# Protect.net
KiCad netlist of a schematic drawn in Altium Designer
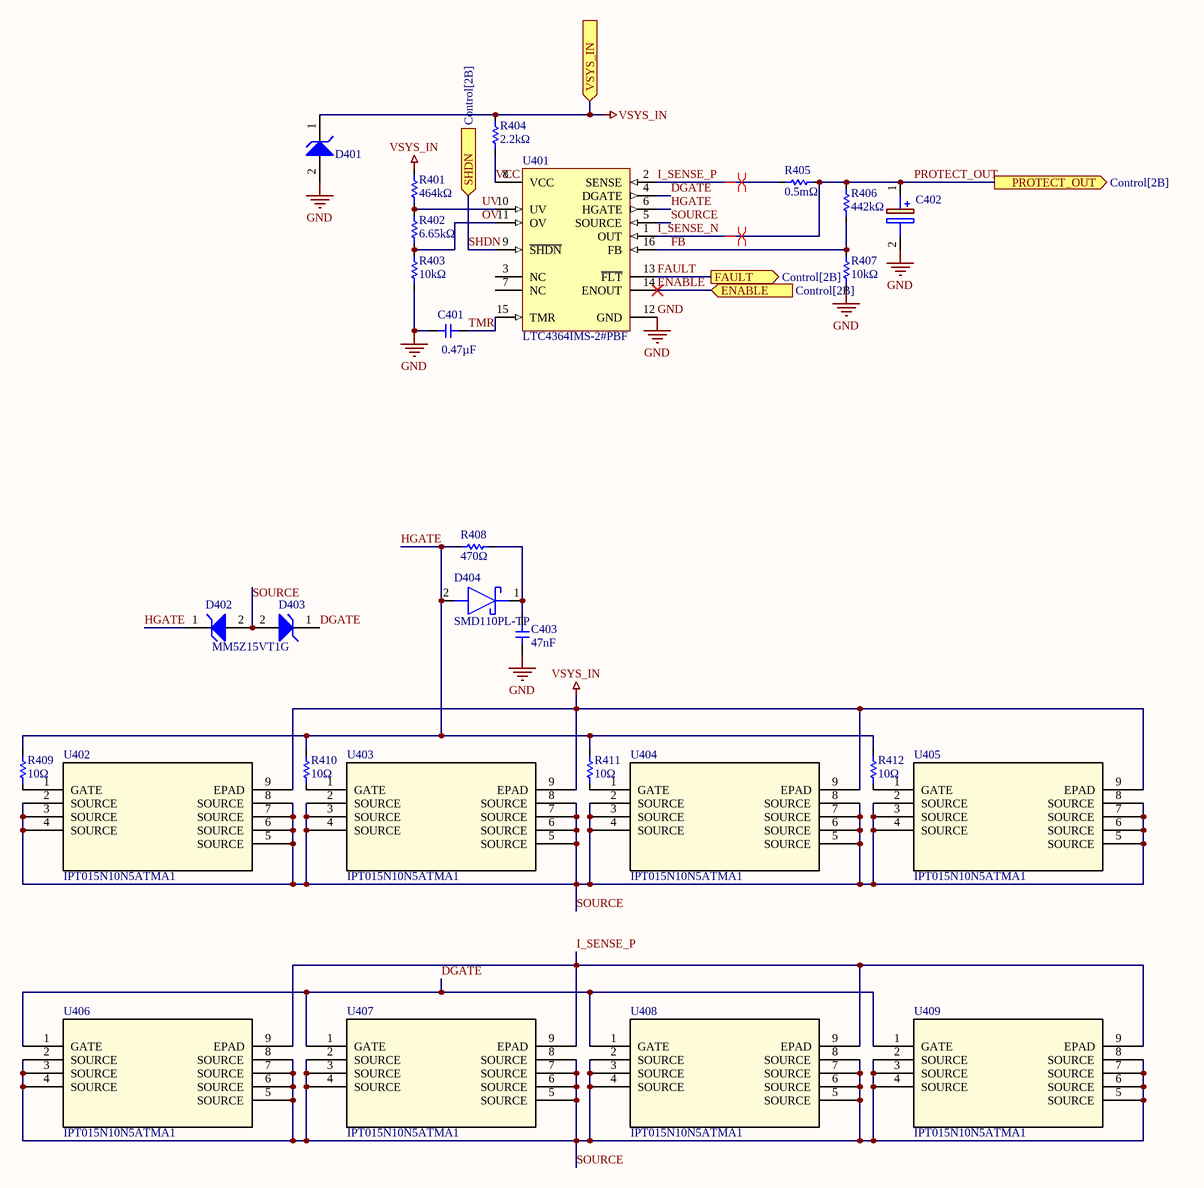
[diagram p0: Protect.SchDoc]

(export (version "E")
  (design (tool "Eeschema 10.0.6"))
  (components
    (comp (ref "C401")
      (value "non-polar_Capacitor")
      (footprint "1210")
      (description "SMD type ceramic capacitor")
      (fields
        (field (name "VOLTAGE") "50V")
        (field (name "CAPACITANCE") "0.47µF")
        (field (name "SOURCE") "robit_passive.SchLib")
      )
      (libsource (lib "robit circuit") (part "Capacitor"))
    )
    (comp (ref "C402")
      (value "B41858C9477M000")
      (footprint "SamacSys:CAPPRD750W90D1800H3700")
      (description "Capacitor Polarised")
      (fields (field (name "MOUSER PART NUMBER") "871-B41858C9477M"))
      (libsource (lib "*") (part "B41858C9477M000"))
    )
    (comp (ref "C403")
      (value "non-polar_Capacitor")
      (footprint "1210")
      (description "SMD type ceramic capacitor")
      (fields
        (field (name "VOLTAGE") "50V")
        (field (name "CAPACITANCE") "47nF")
        (field (name "SOURCE") "robit_passive.SchLib")
      )
      (libsource (lib "robit circuit") (part "Capacitor"))
    )
    (comp (ref "D401")
      (value "1SMB5945BT3G")
      (footprint "ONSC-SMB-2-403A-03_H_V")
      (description "3 W Zener Voltage Regulator, 2-Pin SMB, Pb-Free, Tape and Reel")
      (fields (field (name "MANUFACTURER") "On Semiconductor"))
      (libsource (lib "Altium Content Vault") (part "ONSC-K1A2-2"))
    )
    (comp (ref "D402")
      (value "MM5Z15VT1G")
      (footprint "ONSC-SOD-523-2-502-01_V")
      (description "Zener Voltage Regulator, 500 mW, 2-Pin SOD-523, Pb-Free, Tape and Reel")
      (fields (field (name "MANUFACTURER") "On Semiconductor"))
      (libsource (lib "Altium Content Vault") (part "ONSC-K1A2-2"))
    )
    (comp (ref "D403")
      (value "MM5Z15VT1G")
      (footprint "ONSC-SOD-523-2-502-01_V")
      (description "Zener Voltage Regulator, 500 mW, 2-Pin SOD-523, Pb-Free, Tape and Reel")
      (fields (field (name "MANUFACTURER") "On Semiconductor"))
      (libsource (lib "Altium Content Vault") (part "ONSC-K1A2-2"))
    )
    (comp (ref "D404")
      (value "SMD110PL-TP")
      (footprint "SamacSys:SODFL3616X135N")
      (description "Schottky Diode")
      (fields (field (name "MOUSER PART NUMBER") "833-SMD110PL-TP"))
      (libsource (lib "*") (part "SMD110PL-TP"))
    )
    (comp (ref "R401") (value "464kΩ") (footprint "SMD_0603") (libsource (lib "Resistor") (part "Resistor")))
    (comp (ref "R402") (value "6.65kΩ") (footprint "SMD_0603") (libsource (lib "Resistor") (part "Resistor")))
    (comp (ref "R403") (value "10kΩ") (footprint "SMD_0603") (libsource (lib "Resistor") (part "Resistor")))
    (comp (ref "R404") (value "2.2kΩ") (footprint "SMD_2512") (libsource (lib "Resistor") (part "Resistor")))
    (comp (ref "R405") (value "0.5mΩ") (footprint "SMD_2512") (libsource (lib "Resistor") (part "Resistor")))
    (comp (ref "R406") (value "442kΩ") (footprint "SMD_0603") (libsource (lib "Resistor") (part "Resistor")))
    (comp (ref "R407") (value "10kΩ") (footprint "SMD_0603") (libsource (lib "Resistor") (part "Resistor")))
    (comp (ref "R408")
      (value "470Ω")
      (footprint "SMD_0603")
      (description "0.1W, 0603")
      (libsource (lib "Resistor") (part "Resistor"))
    )
    (comp (ref "R409") (value "10Ω") (footprint "SMD_0603") (libsource (lib "Resistor") (part "Resistor")))
    (comp (ref "R410") (value "10Ω") (footprint "SMD_0603") (libsource (lib "Resistor") (part "Resistor")))
    (comp (ref "R411") (value "10Ω") (footprint "SMD_0603") (libsource (lib "Resistor") (part "Resistor")))
    (comp (ref "R412") (value "10Ω") (footprint "SMD_0603") (libsource (lib "Resistor") (part "Resistor")))
    (comp (ref "U401")
      (value "LTC4364IMS-2#PBF")
      (footprint "LT-MS-16_M")
      (description "Surge Stopper with Ideal Diode, 4 to 80 V Vin, 16-pin SOP (MS-16), -40 to 85 degC, Pb-Free")
      (fields (field (name "MANUFACTURER") "Linear Technology"))
      (libsource (lib "Altium Content Vault") (part "LT-LTC4364-S-16"))
    )
    (comp (ref "U402")
      (value "IPT015N10N5ATMA1")
      (footprint "PG-HSOF-8-1_INF")
      (fields (field (name "COPYRIGHT") "Copyright (C) 2025 Ultra Librarian. All rights reserved."))
      (libsource (lib "IPT015N10N5ATMA1") (part "IPT015N10N5ATMA1"))
    )
    (comp (ref "U403")
      (value "IPT015N10N5ATMA1")
      (footprint "PG-HSOF-8-1_INF")
      (fields (field (name "COPYRIGHT") "Copyright (C) 2025 Ultra Librarian. All rights reserved."))
      (libsource (lib "IPT015N10N5ATMA1") (part "IPT015N10N5ATMA1"))
    )
    (comp (ref "U404")
      (value "IPT015N10N5ATMA1")
      (footprint "PG-HSOF-8-1_INF")
      (fields (field (name "COPYRIGHT") "Copyright (C) 2025 Ultra Librarian. All rights reserved."))
      (libsource (lib "IPT015N10N5ATMA1") (part "IPT015N10N5ATMA1"))
    )
    (comp (ref "U405")
      (value "IPT015N10N5ATMA1")
      (footprint "PG-HSOF-8-1_INF")
      (fields (field (name "COPYRIGHT") "Copyright (C) 2025 Ultra Librarian. All rights reserved."))
      (libsource (lib "IPT015N10N5ATMA1") (part "IPT015N10N5ATMA1"))
    )
    (comp (ref "U406")
      (value "IPT015N10N5ATMA1")
      (footprint "PG-HSOF-8-1_INF")
      (fields (field (name "COPYRIGHT") "Copyright (C) 2025 Ultra Librarian. All rights reserved."))
      (libsource (lib "IPT015N10N5ATMA1") (part "IPT015N10N5ATMA1"))
    )
    (comp (ref "U407")
      (value "IPT015N10N5ATMA1")
      (footprint "PG-HSOF-8-1_INF")
      (fields (field (name "COPYRIGHT") "Copyright (C) 2025 Ultra Librarian. All rights reserved."))
      (libsource (lib "IPT015N10N5ATMA1") (part "IPT015N10N5ATMA1"))
    )
    (comp (ref "U408")
      (value "IPT015N10N5ATMA1")
      (footprint "PG-HSOF-8-1_INF")
      (fields (field (name "COPYRIGHT") "Copyright (C) 2025 Ultra Librarian. All rights reserved."))
      (libsource (lib "IPT015N10N5ATMA1") (part "IPT015N10N5ATMA1"))
    )
    (comp (ref "U409")
      (value "IPT015N10N5ATMA1")
      (footprint "PG-HSOF-8-1_INF")
      (fields (field (name "COPYRIGHT") "Copyright (C) 2025 Ultra Librarian. All rights reserved."))
      (libsource (lib "IPT015N10N5ATMA1") (part "IPT015N10N5ATMA1"))
    )
  )
  (nets
    (net (code "1") (name "/DGATE") (class "Default")
      (node (ref "D403") (pin "1") (pinfunction "K_1") (pintype "passive"))
      (node (ref "U401") (pin "4") (pinfunction "DGATE_4") (pintype "output"))
      (node (ref "U406") (pin "1") (pinfunction "GATE_1") (pintype "passive"))
      (node (ref "U407") (pin "1") (pinfunction "GATE_1") (pintype "passive"))
      (node (ref "U408") (pin "1") (pinfunction "GATE_1") (pintype "passive"))
      (node (ref "U409") (pin "1") (pinfunction "GATE_1") (pintype "passive"))
    )
    (net (code "2") (name "/ENABLE") (class "Default")
      (node (ref "U401") (pin "14") (pinfunction "ENOUT_14") (pintype "tri_state+no_connect"))
    )
    (net (code "3") (name "/FAULT") (class "Default")
      (node (ref "U401") (pin "13") (pinfunction "~{FLT}_13") (pintype "tri_state"))
    )
    (net (code "4") (name "/FB") (class "Default")
      (node (ref "R406") (pin "2") (pinfunction "2_2") (pintype "passive"))
      (node (ref "R407") (pin "1") (pinfunction "1_1") (pintype "passive"))
      (node (ref "U401") (pin "16") (pinfunction "FB_16") (pintype "input"))
    )
    (net (code "5") (name "/HGATE") (class "Default")
      (node (ref "D402") (pin "1") (pinfunction "K_1") (pintype "passive"))
      (node (ref "D404") (pin "2") (pinfunction "A_2") (pintype "passive"))
      (node (ref "R408") (pin "1") (pinfunction "1_1") (pintype "passive"))
      (node (ref "R409") (pin "1") (pinfunction "1_1") (pintype "passive"))
      (node (ref "R410") (pin "1") (pinfunction "1_1") (pintype "passive"))
      (node (ref "R411") (pin "1") (pinfunction "1_1") (pintype "passive"))
      (node (ref "R412") (pin "1") (pinfunction "1_1") (pintype "passive"))
      (node (ref "U401") (pin "6") (pinfunction "HGATE_6") (pintype "output"))
    )
    (net (code "6") (name "/I_SENSE_N") (class "Default")
      (node (ref "C402") (pin "1") (pinfunction "+_1") (pintype "passive"))
      (node (ref "R405") (pin "2") (pinfunction "2_2") (pintype "passive"))
      (node (ref "R406") (pin "1") (pinfunction "1_1") (pintype "passive"))
      (node (ref "U401") (pin "1") (pinfunction "OUT_1") (pintype "input"))
    )
    (net (code "7") (name "/I_SENSE_P") (class "Default")
      (node (ref "R405") (pin "1") (pinfunction "1_1") (pintype "passive"))
      (node (ref "U401") (pin "2") (pinfunction "SENSE_2") (pintype "input"))
      (node (ref "U406") (pin "9") (pinfunction "EPAD_9") (pintype "passive"))
      (node (ref "U407") (pin "9") (pinfunction "EPAD_9") (pintype "passive"))
      (node (ref "U408") (pin "9") (pinfunction "EPAD_9") (pintype "passive"))
      (node (ref "U409") (pin "9") (pinfunction "EPAD_9") (pintype "passive"))
    )
    (net (code "8") (name "/OV") (class "Default")
      (node (ref "R402") (pin "2") (pinfunction "2_2") (pintype "passive"))
      (node (ref "R403") (pin "1") (pinfunction "1_1") (pintype "passive"))
      (node (ref "U401") (pin "11") (pinfunction "OV_11") (pintype "input"))
    )
    (net (code "9") (name "/SHDN") (class "Default")
      (node (ref "U401") (pin "9") (pinfunction "~{SHDN}_9") (pintype "input"))
    )
    (net (code "10") (name "/SOURCE") (class "Default")
      (node (ref "D402") (pin "2") (pinfunction "A_2") (pintype "passive"))
      (node (ref "D403") (pin "2") (pinfunction "A_2") (pintype "passive"))
      (node (ref "U401") (pin "5") (pinfunction "SOURCE_5") (pintype "input"))
      (node (ref "U402") (pin "2") (pinfunction "SOURCE_2") (pintype "passive"))
      (node (ref "U402") (pin "3") (pinfunction "SOURCE_3") (pintype "passive"))
      (node (ref "U402") (pin "4") (pinfunction "SOURCE_4") (pintype "passive"))
      (node (ref "U402") (pin "5") (pinfunction "SOURCE_5") (pintype "passive"))
      (node (ref "U402") (pin "6") (pinfunction "SOURCE_6") (pintype "passive"))
      (node (ref "U402") (pin "7") (pinfunction "SOURCE_7") (pintype "passive"))
      (node (ref "U402") (pin "8") (pinfunction "SOURCE_8") (pintype "passive"))
      (node (ref "U403") (pin "2") (pinfunction "SOURCE_2") (pintype "passive"))
      (node (ref "U403") (pin "3") (pinfunction "SOURCE_3") (pintype "passive"))
      (node (ref "U403") (pin "4") (pinfunction "SOURCE_4") (pintype "passive"))
      (node (ref "U403") (pin "5") (pinfunction "SOURCE_5") (pintype "passive"))
      (node (ref "U403") (pin "6") (pinfunction "SOURCE_6") (pintype "passive"))
      (node (ref "U403") (pin "7") (pinfunction "SOURCE_7") (pintype "passive"))
      (node (ref "U403") (pin "8") (pinfunction "SOURCE_8") (pintype "passive"))
      (node (ref "U404") (pin "2") (pinfunction "SOURCE_2") (pintype "passive"))
      (node (ref "U404") (pin "3") (pinfunction "SOURCE_3") (pintype "passive"))
      (node (ref "U404") (pin "4") (pinfunction "SOURCE_4") (pintype "passive"))
      (node (ref "U404") (pin "5") (pinfunction "SOURCE_5") (pintype "passive"))
      (node (ref "U404") (pin "6") (pinfunction "SOURCE_6") (pintype "passive"))
      (node (ref "U404") (pin "7") (pinfunction "SOURCE_7") (pintype "passive"))
      (node (ref "U404") (pin "8") (pinfunction "SOURCE_8") (pintype "passive"))
      (node (ref "U405") (pin "2") (pinfunction "SOURCE_2") (pintype "passive"))
      (node (ref "U405") (pin "3") (pinfunction "SOURCE_3") (pintype "passive"))
      (node (ref "U405") (pin "4") (pinfunction "SOURCE_4") (pintype "passive"))
      (node (ref "U405") (pin "5") (pinfunction "SOURCE_5") (pintype "passive"))
      (node (ref "U405") (pin "6") (pinfunction "SOURCE_6") (pintype "passive"))
      (node (ref "U405") (pin "7") (pinfunction "SOURCE_7") (pintype "passive"))
      (node (ref "U405") (pin "8") (pinfunction "SOURCE_8") (pintype "passive"))
      (node (ref "U406") (pin "2") (pinfunction "SOURCE_2") (pintype "passive"))
      (node (ref "U406") (pin "3") (pinfunction "SOURCE_3") (pintype "passive"))
      (node (ref "U406") (pin "4") (pinfunction "SOURCE_4") (pintype "passive"))
      (node (ref "U406") (pin "5") (pinfunction "SOURCE_5") (pintype "passive"))
      (node (ref "U406") (pin "6") (pinfunction "SOURCE_6") (pintype "passive"))
      (node (ref "U406") (pin "7") (pinfunction "SOURCE_7") (pintype "passive"))
      (node (ref "U406") (pin "8") (pinfunction "SOURCE_8") (pintype "passive"))
      (node (ref "U407") (pin "2") (pinfunction "SOURCE_2") (pintype "passive"))
      (node (ref "U407") (pin "3") (pinfunction "SOURCE_3") (pintype "passive"))
      (node (ref "U407") (pin "4") (pinfunction "SOURCE_4") (pintype "passive"))
      (node (ref "U407") (pin "5") (pinfunction "SOURCE_5") (pintype "passive"))
      (node (ref "U407") (pin "6") (pinfunction "SOURCE_6") (pintype "passive"))
      (node (ref "U407") (pin "7") (pinfunction "SOURCE_7") (pintype "passive"))
      (node (ref "U407") (pin "8") (pinfunction "SOURCE_8") (pintype "passive"))
      (node (ref "U408") (pin "2") (pinfunction "SOURCE_2") (pintype "passive"))
      (node (ref "U408") (pin "3") (pinfunction "SOURCE_3") (pintype "passive"))
      (node (ref "U408") (pin "4") (pinfunction "SOURCE_4") (pintype "passive"))
      (node (ref "U408") (pin "5") (pinfunction "SOURCE_5") (pintype "passive"))
      (node (ref "U408") (pin "6") (pinfunction "SOURCE_6") (pintype "passive"))
      (node (ref "U408") (pin "7") (pinfunction "SOURCE_7") (pintype "passive"))
      (node (ref "U408") (pin "8") (pinfunction "SOURCE_8") (pintype "passive"))
      (node (ref "U409") (pin "2") (pinfunction "SOURCE_2") (pintype "passive"))
      (node (ref "U409") (pin "3") (pinfunction "SOURCE_3") (pintype "passive"))
      (node (ref "U409") (pin "4") (pinfunction "SOURCE_4") (pintype "passive"))
      (node (ref "U409") (pin "5") (pinfunction "SOURCE_5") (pintype "passive"))
      (node (ref "U409") (pin "6") (pinfunction "SOURCE_6") (pintype "passive"))
      (node (ref "U409") (pin "7") (pinfunction "SOURCE_7") (pintype "passive"))
      (node (ref "U409") (pin "8") (pinfunction "SOURCE_8") (pintype "passive"))
    )
    (net (code "11") (name "/TMR") (class "Default")
      (node (ref "C401") (pin "2") (pinfunction "2_2") (pintype "passive"))
      (node (ref "U401") (pin "15") (pinfunction "TMR_15") (pintype "input"))
    )
    (net (code "12") (name "/UV") (class "Default")
      (node (ref "R401") (pin "2") (pinfunction "2_2") (pintype "passive"))
      (node (ref "R402") (pin "1") (pinfunction "1_1") (pintype "passive"))
      (node (ref "U401") (pin "10") (pinfunction "UV_10") (pintype "input"))
    )
    (net (code "13") (name "/VCC") (class "Default")
      (node (ref "R404") (pin "2") (pinfunction "2_2") (pintype "passive"))
      (node (ref "U401") (pin "8") (pinfunction "VCC_8") (pintype "power_in"))
    )
    (net (code "14") (name "GND") (class "Default")
      (node (ref "C401") (pin "1") (pinfunction "1_1") (pintype "passive"))
      (node (ref "C402") (pin "2") (pinfunction "-_2") (pintype "passive"))
      (node (ref "C403") (pin "1") (pinfunction "1_1") (pintype "passive"))
      (node (ref "D401") (pin "2") (pinfunction "A_2") (pintype "passive"))
      (node (ref "R403") (pin "2") (pinfunction "2_2") (pintype "passive"))
      (node (ref "R407") (pin "2") (pinfunction "2_2") (pintype "passive"))
      (node (ref "U401") (pin "12") (pinfunction "GND_12") (pintype "power_in"))
    )
    (net (code "15") (name "Net-(D404-K)") (class "Default")
      (node (ref "C403") (pin "2") (pinfunction "2_2") (pintype "passive"))
      (node (ref "D404") (pin "1") (pinfunction "K_1") (pintype "passive"))
      (node (ref "R408") (pin "2") (pinfunction "2_2") (pintype "passive"))
    )
    (net (code "16") (name "Net-(U402-GATE)") (class "Default")
      (node (ref "R409") (pin "2") (pinfunction "2_2") (pintype "passive"))
      (node (ref "U402") (pin "1") (pinfunction "GATE_1") (pintype "passive"))
    )
    (net (code "17") (name "Net-(U403-GATE)") (class "Default")
      (node (ref "R410") (pin "2") (pinfunction "2_2") (pintype "passive"))
      (node (ref "U403") (pin "1") (pinfunction "GATE_1") (pintype "passive"))
    )
    (net (code "18") (name "Net-(U404-GATE)") (class "Default")
      (node (ref "R411") (pin "2") (pinfunction "2_2") (pintype "passive"))
      (node (ref "U404") (pin "1") (pinfunction "GATE_1") (pintype "passive"))
    )
    (net (code "19") (name "Net-(U405-GATE)") (class "Default")
      (node (ref "R412") (pin "2") (pinfunction "2_2") (pintype "passive"))
      (node (ref "U405") (pin "1") (pinfunction "GATE_1") (pintype "passive"))
    )
    (net (code "20") (name "VSYS_IN") (class "Default")
      (node (ref "D401") (pin "1") (pinfunction "K_1") (pintype "passive"))
      (node (ref "R401") (pin "1") (pinfunction "1_1") (pintype "passive"))
      (node (ref "R404") (pin "1") (pinfunction "1_1") (pintype "passive"))
      (node (ref "U402") (pin "9") (pinfunction "EPAD_9") (pintype "passive"))
      (node (ref "U403") (pin "9") (pinfunction "EPAD_9") (pintype "passive"))
      (node (ref "U404") (pin "9") (pinfunction "EPAD_9") (pintype "passive"))
      (node (ref "U405") (pin "9") (pinfunction "EPAD_9") (pintype "passive"))
    )
    (net (code "21") (name "unconnected-(U401-NC-Pad3)") (class "Default")
      (node (ref "U401") (pin "3") (pinfunction "NC_3") (pintype "passive"))
    )
    (net (code "22") (name "unconnected-(U401-NC-Pad7)") (class "Default")
      (node (ref "U401") (pin "7") (pinfunction "NC_7") (pintype "passive"))
    )
  )
)
